# mosV1_0.net
KiCad netlist of a schematic drawn in Altium Designer
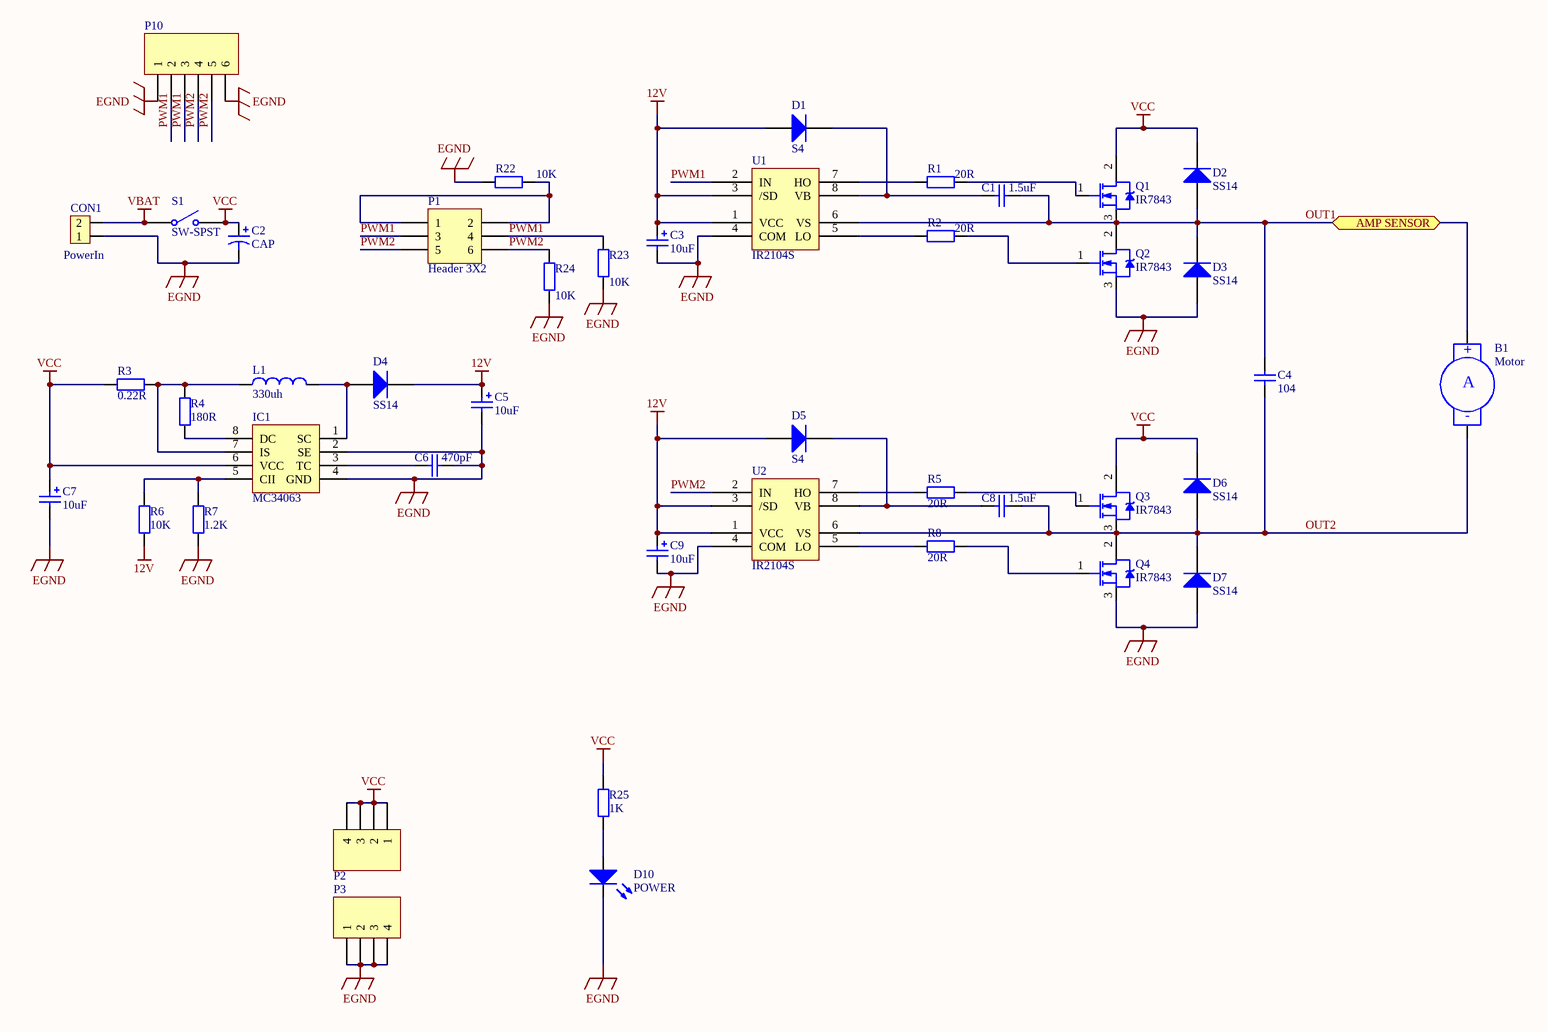
[diagram p0: 自控mosV1.0.SchDoc]

(export (version "E")
  (design (tool "Eeschema 10.0.6"))
  (components
    (comp (ref "B1")
      (value "Motor")
      (footprint "KF301-2P")
      (description "Servo Motor")
      (libsource (lib "landzo_mos") (part "Motor Servo"))
    )
    (comp (ref "C1")
      (value "1.5uF")
      (footprint "C2012")
      (description "Capacitor")
      (fields (field (name "Comment") "Cap") (field (name "PUBLISHER") "Altium Limited"))
      (libsource (lib "Miscellaneous Devices") (part "Cap"))
    )
    (comp (ref "C2") (value "CAP") (footprint "SMD-EC-F5") (libsource (lib "电赛") (part "CAP+")))
    (comp (ref "C3")
      (value "10uF")
      (footprint "C2012")
      (description "Polarized Capacitor (Radial)")
      (fields (field (name "Comment") "Cap Pol1") (field (name "PUBLISHER") "Altium Limited"))
      (libsource (lib "landzo_mos") (part "Cap Pol1"))
    )
    (comp (ref "C4")
      (value "104")
      (footprint "C2012")
      (description "Capacitor")
      (fields (field (name "Comment") "Cap") (field (name "PUBLISHER") "Altium Limited"))
      (libsource (lib "Miscellaneous Devices") (part "Cap"))
    )
    (comp (ref "C5")
      (value "10uF")
      (footprint "1206C")
      (description "Polarized Capacitor (Radial)")
      (fields (field (name "Comment") "Cap Pol1") (field (name "PUBLISHER") "Altium Limited"))
      (libsource (lib "landzo_mos") (part "Cap Pol1"))
    )
    (comp (ref "C6")
      (value "470pF")
      (footprint "C2012")
      (description "Capacitor")
      (fields (field (name "Comment") "Cap") (field (name "PUBLISHER") "Altium Limited"))
      (libsource (lib "Miscellaneous Devices") (part "Cap"))
    )
    (comp (ref "C7")
      (value "10uF")
      (footprint "1206C")
      (description "Polarized Capacitor (Radial)")
      (fields (field (name "Comment") "Cap Pol1") (field (name "PUBLISHER") "Altium Limited"))
      (libsource (lib "landzo_mos") (part "Cap Pol1"))
    )
    (comp (ref "C8")
      (value "1.5uF")
      (footprint "C2012")
      (description "Capacitor")
      (fields (field (name "Comment") "Cap") (field (name "PUBLISHER") "Altium Limited"))
      (libsource (lib "Miscellaneous Devices") (part "Cap"))
    )
    (comp (ref "C9")
      (value "10uF")
      (footprint "C2012")
      (description "Polarized Capacitor (Radial)")
      (fields (field (name "Comment") "Cap Pol1") (field (name "PUBLISHER") "Altium Limited"))
      (libsource (lib "landzo_mos") (part "Cap Pol1"))
    )
    (comp (ref "CON1")
      (value "PowerIn")
      (footprint "KF301-2P")
      (description "Header, 2-Pin")
      (libsource (lib "landzo_mos") (part "Header 2"))
    )
    (comp (ref "D1")
      (value "S4")
      (footprint "R2012")
      (description "1 Amp General Purpose Rectifier")
      (fields (field (name "PUBLISHER") "Altium Limited"))
      (libsource (lib "Miscellaneous Devices") (part "Diode 1N4007"))
    )
    (comp (ref "D2")
      (value "SS14")
      (footprint "hole-chip diode")
      (description "1 Amp General Purpose Rectifier")
      (fields (field (name "PUBLISHER") "Altium Limited"))
      (libsource (lib "Miscellaneous Devices") (part "Diode 1N4007"))
    )
    (comp (ref "D3")
      (value "SS14")
      (footprint "hole-chip diode")
      (description "1 Amp General Purpose Rectifier")
      (fields (field (name "PUBLISHER") "Altium Limited"))
      (libsource (lib "Miscellaneous Devices") (part "Diode 1N4007"))
    )
    (comp (ref "D4")
      (value "SS14")
      (footprint "hole-chip diode")
      (description "1 Amp General Purpose Rectifier")
      (fields (field (name "PUBLISHER") "Altium Limited"))
      (libsource (lib "Miscellaneous Devices") (part "Diode 1N4007"))
    )
    (comp (ref "D5")
      (value "S4")
      (footprint "R2012")
      (description "1 Amp General Purpose Rectifier")
      (fields (field (name "PUBLISHER") "Altium Limited"))
      (libsource (lib "Miscellaneous Devices") (part "Diode 1N4007"))
    )
    (comp (ref "D6")
      (value "SS14")
      (footprint "hole-chip diode")
      (description "1 Amp General Purpose Rectifier")
      (fields (field (name "PUBLISHER") "Altium Limited"))
      (libsource (lib "Miscellaneous Devices") (part "Diode 1N4007"))
    )
    (comp (ref "D7")
      (value "SS14")
      (footprint "hole-chip diode")
      (description "1 Amp General Purpose Rectifier")
      (fields (field (name "PUBLISHER") "Altium Limited"))
      (libsource (lib "Miscellaneous Devices") (part "Diode 1N4007"))
    )
    (comp (ref "D10")
      (value "POWER")
      (footprint "C2012")
      (description "Typical INFRARED GaAs LED")
      (libsource (lib "K60-V4.0") (part "LED"))
    )
    (comp (ref "IC1")
      (value "MC34063")
      (footprint "MOS motor driving module:MC34063")
      (libsource (lib "Landzo") (part "MC34063"))
    )
    (comp (ref "L1")
      (value "330uh")
      (footprint "SMD-EC-F12.5")
      (description "Inductor")
      (fields (field (name "PUBLISHER") "Altium Limited"))
      (libsource (lib "landzo_mos") (part "Inductor"))
    )
    (comp (ref "P1")
      (value "Header 3X2")
      (footprint "HDR2X3")
      (description "Header, 3-Pin, Dual row")
      (fields (field (name "PUBLISHER") "Altium Limited"))
      (libsource (lib "Miscellaneous Connectors") (part "Header 3X2"))
    )
    (comp (ref "P2")
      (value "Header 4")
      (footprint "HDR1X4")
      (description "Header, 4-Pin")
      (fields (field (name "PUBLISHER") "Altium Limited"))
      (libsource (lib "Sparks") (part "Header 4"))
    )
    (comp (ref "P3")
      (value "Header 4")
      (footprint "HDR1X4")
      (description "Header, 4-Pin")
      (fields (field (name "PUBLISHER") "Altium Limited"))
      (libsource (lib "") (part "Header 4_1"))
    )
    (comp (ref "P10")
      (value "Header 6")
      (footprint "FFC/SM1.0-2H6")
      (description "Header, 6-Pin")
      (fields (field (name "PUBLISHER") "Altium Limited"))
      (libsource (lib "Miscellaneous Connectors") (part "Header 6"))
    )
    (comp (ref "Q1")
      (value "IR7843")
      (footprint "LR7843")
      (description "N-Channel Power MOSFET")
      (fields (field (name "PUBLISHER") "Altium Limited"))
      (libsource (lib "MOS motor driving module ") (part "NMOS-2"))
    )
    (comp (ref "Q2")
      (value "IR7843")
      (footprint "LR7843")
      (description "N-Channel Power MOSFET")
      (fields (field (name "PUBLISHER") "Altium Limited"))
      (libsource (lib "MOS motor driving module ") (part "NMOS-2"))
    )
    (comp (ref "Q3")
      (value "IR7843")
      (footprint "LR7843")
      (description "N-Channel Power MOSFET")
      (fields (field (name "PUBLISHER") "Altium Limited"))
      (libsource (lib "MOS motor driving module ") (part "NMOS-2"))
    )
    (comp (ref "Q4")
      (value "IR7843")
      (footprint "LR7843")
      (description "N-Channel Power MOSFET")
      (fields (field (name "PUBLISHER") "Altium Limited"))
      (libsource (lib "MOS motor driving module ") (part "NMOS-2"))
    )
    (comp (ref "R1")
      (value "20R")
      (footprint "R2012")
      (description "Resistor")
      (fields (field (name "Comment") "Res2") (field (name "PUBLISHER") "Altium Limited"))
      (libsource (lib "landzo_mos") (part "Res2"))
    )
    (comp (ref "R2")
      (value "20R")
      (footprint "R2012")
      (description "Resistor")
      (fields (field (name "Comment") "Res2") (field (name "PUBLISHER") "Altium Limited"))
      (libsource (lib "landzo_mos") (part "Res2"))
    )
    (comp (ref "R3")
      (value "0.22R")
      (footprint "SK54")
      (description "Resistor")
      (fields (field (name "Comment") "Res2") (field (name "PUBLISHER") "Altium Limited"))
      (libsource (lib "landzo_mos") (part "Res2"))
    )
    (comp (ref "R4")
      (value "180R")
      (footprint "R2012")
      (description "Resistor")
      (fields (field (name "Comment") "Res2") (field (name "PUBLISHER") "Altium Limited"))
      (libsource (lib "") (part "Res2_1"))
    )
    (comp (ref "R5")
      (value "20R")
      (footprint "R2012")
      (description "Resistor")
      (fields (field (name "Comment") "Res2") (field (name "PUBLISHER") "Altium Limited"))
      (libsource (lib "landzo_mos") (part "Res2"))
    )
    (comp (ref "R6")
      (value "10K")
      (footprint "R2012")
      (description "Resistor")
      (fields (field (name "Comment") "Res2") (field (name "PUBLISHER") "Altium Limited"))
      (libsource (lib "") (part "Res2_1"))
    )
    (comp (ref "R7")
      (value "1.2K")
      (footprint "R2012")
      (description "Resistor")
      (fields (field (name "Comment") "Res2") (field (name "PUBLISHER") "Altium Limited"))
      (libsource (lib "") (part "Res2_1"))
    )
    (comp (ref "R8")
      (value "20R")
      (footprint "R2012")
      (description "Resistor")
      (fields (field (name "Comment") "Res2") (field (name "PUBLISHER") "Altium Limited"))
      (libsource (lib "landzo_mos") (part "Res2"))
    )
    (comp (ref "R22")
      (value "10K")
      (footprint "1206(2)")
      (description "Resistor")
      (fields (field (name "Comment") "Res2") (field (name "PUBLISHER") "Altium Limited"))
      (libsource (lib "Miscellaneous Devices") (part "Res2"))
    )
    (comp (ref "R23")
      (value "10K")
      (footprint "R2012")
      (description "Resistor")
      (fields (field (name "Comment") "Res2") (field (name "PUBLISHER") "Altium Limited"))
      (libsource (lib "") (part "Res2_1"))
    )
    (comp (ref "R24")
      (value "10K")
      (footprint "R2012")
      (description "Resistor")
      (fields (field (name "Comment") "Res2") (field (name "PUBLISHER") "Altium Limited"))
      (libsource (lib "") (part "Res2_1"))
    )
    (comp (ref "R25")
      (value "1K")
      (footprint "R2012")
      (description "Resistor of led")
      (libsource (lib "K60-V4.0") (part "Res"))
    )
    (comp (ref "S1")
      (value "SW-SPST")
      (footprint "SW-125V6A(-)")
      (description "Single-Pole, Single-Throw Switch")
      (fields (field (name "PUBLISHER") "Altium Limited"))
      (libsource (lib "Miscellaneous Devices") (part "SW-SPST"))
    )
    (comp (ref "U1")
      (value "IR2104S")
      (footprint "IR2104")
      (libsource (lib "MOS motor driving module ") (part "Component_1_1"))
    )
    (comp (ref "U2")
      (value "IR2104S")
      (footprint "IR2104")
      (libsource (lib "MOS motor driving module ") (part "Component_1_1"))
    )
  )
  (nets
    (net (code "1") (name "/OUT1") (class "Default")
      (node (ref "B1") (pin "1") (pinfunction "+_1") (pintype "passive"))
      (node (ref "C1") (pin "1") (pinfunction "1_1") (pintype "passive"))
      (node (ref "C4") (pin "1") (pinfunction "1_1") (pintype "passive"))
      (node (ref "D2") (pin "1") (pinfunction "A_1") (pintype "passive"))
      (node (ref "D3") (pin "2") (pinfunction "K_2") (pintype "passive"))
      (node (ref "Q1") (pin "3") (pinfunction "S_3") (pintype "passive"))
      (node (ref "Q2") (pin "2") (pinfunction "D_2") (pintype "passive"))
      (node (ref "U1") (pin "6") (pinfunction "VS_6") (pintype "passive"))
    )
    (net (code "2") (name "/OUT2") (class "Default")
      (node (ref "B1") (pin "2") (pinfunction "-_2") (pintype "passive"))
      (node (ref "C4") (pin "2") (pinfunction "2_2") (pintype "passive"))
      (node (ref "C8") (pin "1") (pinfunction "1_1") (pintype "passive"))
      (node (ref "D6") (pin "1") (pinfunction "A_1") (pintype "passive"))
      (node (ref "D7") (pin "2") (pinfunction "K_2") (pintype "passive"))
      (node (ref "Q3") (pin "3") (pinfunction "S_3") (pintype "passive"))
      (node (ref "Q4") (pin "2") (pinfunction "D_2") (pintype "passive"))
      (node (ref "U2") (pin "6") (pinfunction "VS_6") (pintype "passive"))
    )
    (net (code "3") (name "/PWM1") (class "Default")
      (node (ref "P1") (pin "3") (pinfunction "3_3") (pintype "passive"))
      (node (ref "P1") (pin "4") (pinfunction "4_4") (pintype "passive"))
      (node (ref "P10") (pin "2") (pinfunction "2_2") (pintype "passive"))
      (node (ref "P10") (pin "3") (pinfunction "3_3") (pintype "passive"))
      (node (ref "R23") (pin "2") (pinfunction "2_2") (pintype "passive"))
      (node (ref "U1") (pin "2") (pinfunction "IN_2") (pintype "passive"))
    )
    (net (code "4") (name "/PWM2") (class "Default")
      (node (ref "P1") (pin "5") (pinfunction "5_5") (pintype "passive"))
      (node (ref "P1") (pin "6") (pinfunction "6_6") (pintype "passive"))
      (node (ref "P10") (pin "4") (pinfunction "4_4") (pintype "passive"))
      (node (ref "P10") (pin "5") (pinfunction "5_5") (pintype "passive"))
      (node (ref "R24") (pin "2") (pinfunction "2_2") (pintype "passive"))
      (node (ref "U2") (pin "2") (pinfunction "IN_2") (pintype "passive"))
    )
    (net (code "5") (name "12V") (class "Default")
      (node (ref "C3") (pin "1") (pinfunction "1_1") (pintype "passive"))
      (node (ref "C5") (pin "1") (pinfunction "1_1") (pintype "passive"))
      (node (ref "C9") (pin "1") (pinfunction "1_1") (pintype "passive"))
      (node (ref "D1") (pin "1") (pinfunction "A_1") (pintype "passive"))
      (node (ref "D4") (pin "2") (pinfunction "K_2") (pintype "passive"))
      (node (ref "D5") (pin "1") (pinfunction "A_1") (pintype "passive"))
      (node (ref "R6") (pin "1") (pinfunction "1_1") (pintype "passive"))
      (node (ref "U1") (pin "1") (pinfunction "VCC_1") (pintype "passive"))
      (node (ref "U1") (pin "3") (pinfunction "/SD_3") (pintype "passive"))
      (node (ref "U2") (pin "1") (pinfunction "VCC_1") (pintype "passive"))
      (node (ref "U2") (pin "3") (pinfunction "/SD_3") (pintype "passive"))
    )
    (net (code "6") (name "EGND") (class "Default")
      (node (ref "C2") (pin "2") (pinfunction "2_2") (pintype "passive"))
      (node (ref "C3") (pin "2") (pinfunction "2_2") (pintype "passive"))
      (node (ref "C5") (pin "2") (pinfunction "2_2") (pintype "passive"))
      (node (ref "C6") (pin "1") (pinfunction "1_1") (pintype "passive"))
      (node (ref "C7") (pin "2") (pinfunction "2_2") (pintype "passive"))
      (node (ref "C9") (pin "2") (pinfunction "2_2") (pintype "passive"))
      (node (ref "CON1") (pin "1") (pinfunction "1_1") (pintype "passive"))
      (node (ref "D10") (pin "2") (pinfunction "2_2") (pintype "passive"))
      (node (ref "D3") (pin "1") (pinfunction "A_1") (pintype "passive"))
      (node (ref "D7") (pin "1") (pinfunction "A_1") (pintype "passive"))
      (node (ref "IC1") (pin "2") (pinfunction "SE_2") (pintype "passive"))
      (node (ref "IC1") (pin "4") (pinfunction "GND_4") (pintype "passive"))
      (node (ref "P10") (pin "1") (pinfunction "1_1") (pintype "passive"))
      (node (ref "P10") (pin "6") (pinfunction "6_6") (pintype "passive"))
      (node (ref "P3") (pin "1") (pinfunction "1_1") (pintype "passive"))
      (node (ref "P3") (pin "2") (pinfunction "2_2") (pintype "passive"))
      (node (ref "P3") (pin "3") (pinfunction "3_3") (pintype "passive"))
      (node (ref "P3") (pin "4") (pinfunction "4_4") (pintype "passive"))
      (node (ref "Q2") (pin "3") (pinfunction "S_3") (pintype "passive"))
      (node (ref "Q4") (pin "3") (pinfunction "S_3") (pintype "passive"))
      (node (ref "R22") (pin "1") (pinfunction "1_1") (pintype "passive"))
      (node (ref "R23") (pin "1") (pinfunction "1_1") (pintype "passive"))
      (node (ref "R24") (pin "1") (pinfunction "1_1") (pintype "passive"))
      (node (ref "R7") (pin "1") (pinfunction "1_1") (pintype "passive"))
      (node (ref "U1") (pin "4") (pinfunction "COM_4") (pintype "passive"))
      (node (ref "U2") (pin "4") (pinfunction "COM_4") (pintype "passive"))
    )
    (net (code "7") (name "Net-(D1-K)") (class "Default")
      (node (ref "C1") (pin "2") (pinfunction "2_2") (pintype "passive"))
      (node (ref "D1") (pin "2") (pinfunction "K_2") (pintype "passive"))
      (node (ref "U1") (pin "8") (pinfunction "VB_8") (pintype "passive"))
    )
    (net (code "8") (name "Net-(D4-A)") (class "Default")
      (node (ref "D4") (pin "1") (pinfunction "A_1") (pintype "passive"))
      (node (ref "IC1") (pin "1") (pinfunction "SC_1") (pintype "passive"))
      (node (ref "L1") (pin "2") (pinfunction "2_2") (pintype "passive"))
    )
    (net (code "9") (name "Net-(D5-K)") (class "Default")
      (node (ref "C8") (pin "2") (pinfunction "2_2") (pintype "passive"))
      (node (ref "D5") (pin "2") (pinfunction "K_2") (pintype "passive"))
      (node (ref "U2") (pin "8") (pinfunction "VB_8") (pintype "passive"))
    )
    (net (code "10") (name "Net-(D10-Pad1)") (class "Default")
      (node (ref "D10") (pin "1") (pinfunction "1_1") (pintype "passive"))
      (node (ref "R25") (pin "1") (pinfunction "1_1") (pintype "passive"))
    )
    (net (code "11") (name "Net-(IC1-CII)") (class "Default")
      (node (ref "IC1") (pin "5") (pinfunction "CII_5") (pintype "passive"))
      (node (ref "R6") (pin "2") (pinfunction "2_2") (pintype "passive"))
      (node (ref "R7") (pin "2") (pinfunction "2_2") (pintype "passive"))
    )
    (net (code "12") (name "Net-(IC1-DC)") (class "Default")
      (node (ref "IC1") (pin "8") (pinfunction "DC_8") (pintype "passive"))
      (node (ref "R4") (pin "1") (pinfunction "1_1") (pintype "passive"))
    )
    (net (code "13") (name "Net-(IC1-IS)") (class "Default")
      (node (ref "IC1") (pin "7") (pinfunction "IS_7") (pintype "passive"))
      (node (ref "L1") (pin "1") (pinfunction "1_1") (pintype "passive"))
      (node (ref "R3") (pin "2") (pinfunction "2_2") (pintype "passive"))
      (node (ref "R4") (pin "2") (pinfunction "2_2") (pintype "passive"))
    )
    (net (code "14") (name "Net-(IC1-TC)") (class "Default")
      (node (ref "C6") (pin "2") (pinfunction "2_2") (pintype "passive"))
      (node (ref "IC1") (pin "3") (pinfunction "TC_3") (pintype "passive"))
    )
    (net (code "15") (name "Net-(P1-Pad1)") (class "Default")
      (node (ref "P1") (pin "1") (pinfunction "1_1") (pintype "passive"))
      (node (ref "P1") (pin "2") (pinfunction "2_2") (pintype "passive"))
      (node (ref "R22") (pin "2") (pinfunction "2_2") (pintype "passive"))
    )
    (net (code "16") (name "Net-(Q1-G)") (class "Default")
      (node (ref "Q1") (pin "1") (pinfunction "G_1") (pintype "passive"))
      (node (ref "R1") (pin "2") (pinfunction "2_2") (pintype "passive"))
    )
    (net (code "17") (name "Net-(Q2-G)") (class "Default")
      (node (ref "Q2") (pin "1") (pinfunction "G_1") (pintype "passive"))
      (node (ref "R2") (pin "2") (pinfunction "2_2") (pintype "passive"))
    )
    (net (code "18") (name "Net-(Q3-G)") (class "Default")
      (node (ref "Q3") (pin "1") (pinfunction "G_1") (pintype "passive"))
      (node (ref "R5") (pin "2") (pinfunction "2_2") (pintype "passive"))
    )
    (net (code "19") (name "Net-(Q4-G)") (class "Default")
      (node (ref "Q4") (pin "1") (pinfunction "G_1") (pintype "passive"))
      (node (ref "R8") (pin "2") (pinfunction "2_2") (pintype "passive"))
    )
    (net (code "20") (name "Net-(U1-HO)") (class "Default")
      (node (ref "R1") (pin "1") (pinfunction "1_1") (pintype "passive"))
      (node (ref "U1") (pin "7") (pinfunction "HO_7") (pintype "passive"))
    )
    (net (code "21") (name "Net-(U1-LO)") (class "Default")
      (node (ref "R2") (pin "1") (pinfunction "1_1") (pintype "passive"))
      (node (ref "U1") (pin "5") (pinfunction "LO_5") (pintype "passive"))
    )
    (net (code "22") (name "Net-(U2-HO)") (class "Default")
      (node (ref "R5") (pin "1") (pinfunction "1_1") (pintype "passive"))
      (node (ref "U2") (pin "7") (pinfunction "HO_7") (pintype "passive"))
    )
    (net (code "23") (name "Net-(U2-LO)") (class "Default")
      (node (ref "R8") (pin "1") (pinfunction "1_1") (pintype "passive"))
      (node (ref "U2") (pin "5") (pinfunction "LO_5") (pintype "passive"))
    )
    (net (code "24") (name "VBAT") (class "Default")
      (node (ref "CON1") (pin "2") (pinfunction "2_2") (pintype "passive"))
      (node (ref "S1") (pin "1") (pinfunction "COMMON_1") (pintype "passive"))
    )
    (net (code "25") (name "VCC") (class "Default")
      (node (ref "C2") (pin "1") (pinfunction "1_1") (pintype "passive"))
      (node (ref "C7") (pin "1") (pinfunction "1_1") (pintype "passive"))
      (node (ref "D2") (pin "2") (pinfunction "K_2") (pintype "passive"))
      (node (ref "D6") (pin "2") (pinfunction "K_2") (pintype "passive"))
      (node (ref "IC1") (pin "6") (pinfunction "VCC_6") (pintype "passive"))
      (node (ref "P2") (pin "1") (pinfunction "1_1") (pintype "passive"))
      (node (ref "P2") (pin "2") (pinfunction "2_2") (pintype "passive"))
      (node (ref "P2") (pin "3") (pinfunction "3_3") (pintype "passive"))
      (node (ref "P2") (pin "4") (pinfunction "4_4") (pintype "passive"))
      (node (ref "Q1") (pin "2") (pinfunction "D_2") (pintype "passive"))
      (node (ref "Q3") (pin "2") (pinfunction "D_2") (pintype "passive"))
      (node (ref "R25") (pin "2") (pinfunction "2_2") (pintype "passive"))
      (node (ref "R3") (pin "1") (pinfunction "1_1") (pintype "passive"))
      (node (ref "S1") (pin "2") (pinfunction "NO_2") (pintype "passive"))
    )
  )
)
